# MainConnector.net
KiCad netlist of a schematic drawn in Altium Designer
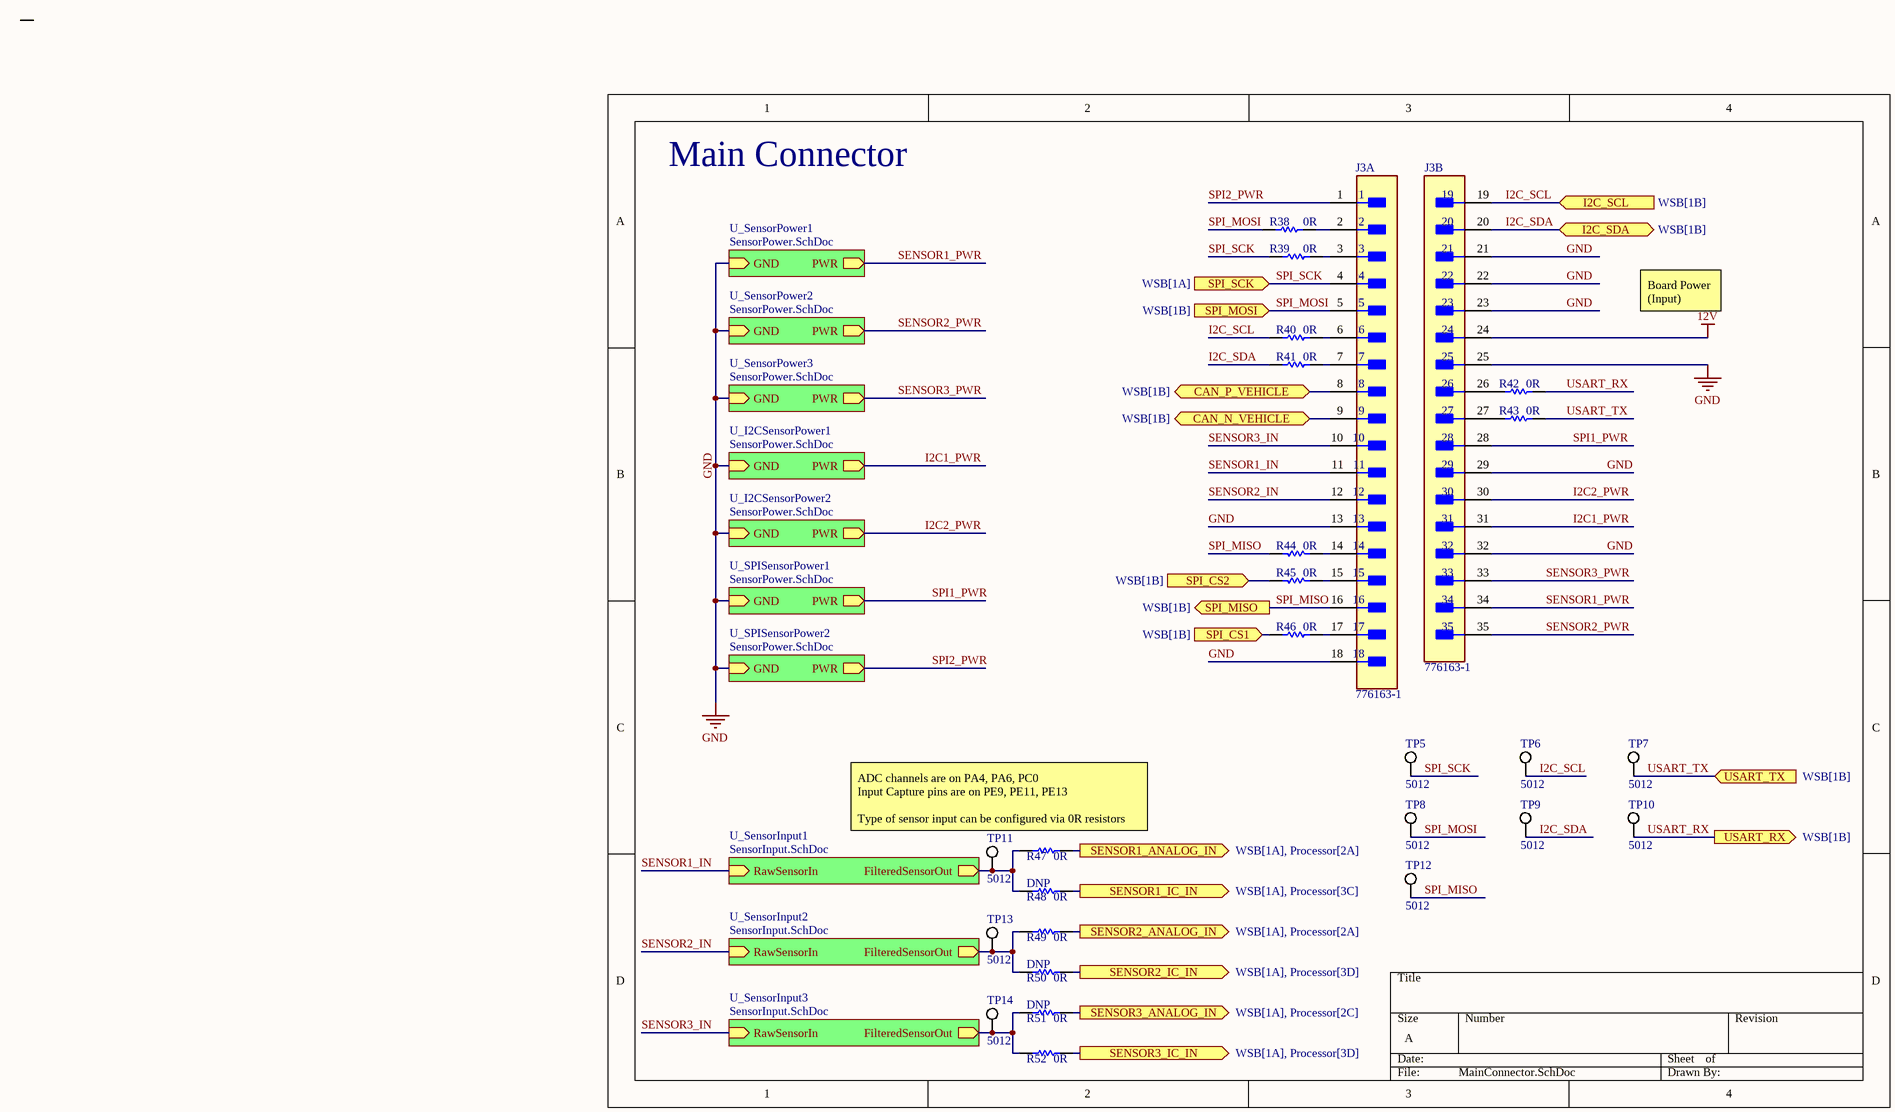
[diagram p0: MainConnector.SchDoc]

(export (version "E")
  (design (tool "Eeschema 10.0.6"))
  (components
    (comp (ref "J3")
      (value "776163-1")
      (footprint "FP-776163-1-MFG")
      (description "CONN HEADER R/A 35POS 4MM")
      (libsource (lib "") (part "519b18991870a11d3ebcd8ad3c0113e_1"))
    )
    (comp (ref "R38")
      (value "RC0805JR-100RL")
      (footprint "RESC2013X60X35LL10T20")
      (description "Chip Resistor, 0 Ohm, +/- 5%, 125 mW, -55 to 155 degC, 0805 (2012 Metric), RoHS, Tape and Reel")
      (fields (field (name "MANUFACTURER") "Yageo") (field (name "RESISTANCE") "0R"))
      (libsource (lib "Altium Content Vault") (part "RES-2"))
    )
    (comp (ref "R39")
      (value "RC0805JR-100RL")
      (footprint "RESC2013X60X35LL10T20")
      (description "Chip Resistor, 0 Ohm, +/- 5%, 125 mW, -55 to 155 degC, 0805 (2012 Metric), RoHS, Tape and Reel")
      (fields (field (name "MANUFACTURER") "Yageo") (field (name "RESISTANCE") "0R"))
      (libsource (lib "Altium Content Vault") (part "RES-2"))
    )
    (comp (ref "R40")
      (value "RC0805JR-100RL")
      (footprint "RESC2013X60X35LL10T20")
      (description "Chip Resistor, 0 Ohm, +/- 5%, 125 mW, -55 to 155 degC, 0805 (2012 Metric), RoHS, Tape and Reel")
      (fields (field (name "MANUFACTURER") "Yageo") (field (name "RESISTANCE") "0R"))
      (libsource (lib "Altium Content Vault") (part "RES-2"))
    )
    (comp (ref "R41")
      (value "RC0805JR-100RL")
      (footprint "RESC2013X60X35LL10T20")
      (description "Chip Resistor, 0 Ohm, +/- 5%, 125 mW, -55 to 155 degC, 0805 (2012 Metric), RoHS, Tape and Reel")
      (fields (field (name "MANUFACTURER") "Yageo") (field (name "RESISTANCE") "0R"))
      (libsource (lib "Altium Content Vault") (part "RES-2"))
    )
    (comp (ref "R42")
      (value "RC0805JR-100RL")
      (footprint "RESC2013X60X35LL10T20")
      (description "Chip Resistor, 0 Ohm, +/- 5%, 125 mW, -55 to 155 degC, 0805 (2012 Metric), RoHS, Tape and Reel")
      (fields (field (name "MANUFACTURER") "Yageo") (field (name "RESISTANCE") "0R"))
      (libsource (lib "Altium Content Vault") (part "RES-2"))
    )
    (comp (ref "R43")
      (value "RC0805JR-100RL")
      (footprint "RESC2013X60X35LL10T20")
      (description "Chip Resistor, 0 Ohm, +/- 5%, 125 mW, -55 to 155 degC, 0805 (2012 Metric), RoHS, Tape and Reel")
      (fields (field (name "MANUFACTURER") "Yageo") (field (name "RESISTANCE") "0R"))
      (libsource (lib "Altium Content Vault") (part "RES-2"))
    )
    (comp (ref "R44")
      (value "RC0805JR-100RL")
      (footprint "RESC2013X60X35LL10T20")
      (description "Chip Resistor, 0 Ohm, +/- 5%, 125 mW, -55 to 155 degC, 0805 (2012 Metric), RoHS, Tape and Reel")
      (fields (field (name "MANUFACTURER") "Yageo") (field (name "RESISTANCE") "0R"))
      (libsource (lib "Altium Content Vault") (part "RES-2"))
    )
    (comp (ref "R45")
      (value "RC0805JR-100RL")
      (footprint "RESC2013X60X35LL10T20")
      (description "Chip Resistor, 0 Ohm, +/- 5%, 125 mW, -55 to 155 degC, 0805 (2012 Metric), RoHS, Tape and Reel")
      (fields (field (name "MANUFACTURER") "Yageo") (field (name "RESISTANCE") "0R"))
      (libsource (lib "Altium Content Vault") (part "RES-2"))
    )
    (comp (ref "R46")
      (value "RC0805JR-100RL")
      (footprint "RESC2013X60X35LL10T20")
      (description "Chip Resistor, 0 Ohm, +/- 5%, 125 mW, -55 to 155 degC, 0805 (2012 Metric), RoHS, Tape and Reel")
      (fields (field (name "MANUFACTURER") "Yageo") (field (name "RESISTANCE") "0R"))
      (libsource (lib "Altium Content Vault") (part "RES-2"))
    )
    (comp (ref "R47")
      (value "RC0805JR-100RL")
      (footprint "RESC2013X60X35LL10T20")
      (description "Chip Resistor, 0 Ohm, +/- 5%, 125 mW, -55 to 155 degC, 0805 (2012 Metric), RoHS, Tape and Reel")
      (fields (field (name "MANUFACTURER") "Yageo") (field (name "RESISTANCE") "0R"))
      (libsource (lib "Altium Content Vault") (part "RES-2"))
    )
    (comp (ref "R48")
      (value "RC0805JR-100RL")
      (footprint "RESC2013X60X35LL10T20")
      (description "Chip Resistor, 0 Ohm, +/- 5%, 125 mW, -55 to 155 degC, 0805 (2012 Metric), RoHS, Tape and Reel")
      (fields
        (field (name "MANUFACTURER") "Yageo")
        (field (name "RESISTANCE") "0R")
        (field (name "DNP") "DNP")
      )
      (libsource (lib "Altium Content Vault") (part "RES-2"))
    )
    (comp (ref "R49")
      (value "RC0805JR-100RL")
      (footprint "RESC2013X60X35LL10T20")
      (description "Chip Resistor, 0 Ohm, +/- 5%, 125 mW, -55 to 155 degC, 0805 (2012 Metric), RoHS, Tape and Reel")
      (fields (field (name "MANUFACTURER") "Yageo") (field (name "RESISTANCE") "0R"))
      (libsource (lib "Altium Content Vault") (part "RES-2"))
    )
    (comp (ref "R50")
      (value "RC0805JR-100RL")
      (footprint "RESC2013X60X35LL10T20")
      (description "Chip Resistor, 0 Ohm, +/- 5%, 125 mW, -55 to 155 degC, 0805 (2012 Metric), RoHS, Tape and Reel")
      (fields
        (field (name "MANUFACTURER") "Yageo")
        (field (name "RESISTANCE") "0R")
        (field (name "DNP") "DNP")
      )
      (libsource (lib "Altium Content Vault") (part "RES-2"))
    )
    (comp (ref "R51")
      (value "RC0805JR-100RL")
      (footprint "RESC2013X60X35LL10T20")
      (description "Chip Resistor, 0 Ohm, +/- 5%, 125 mW, -55 to 155 degC, 0805 (2012 Metric), RoHS, Tape and Reel")
      (fields
        (field (name "MANUFACTURER") "Yageo")
        (field (name "RESISTANCE") "0R")
        (field (name "DNP") "DNP")
      )
      (libsource (lib "Altium Content Vault") (part "RES-2"))
    )
    (comp (ref "R52")
      (value "RC0805JR-100RL")
      (footprint "RESC2013X60X35LL10T20")
      (description "Chip Resistor, 0 Ohm, +/- 5%, 125 mW, -55 to 155 degC, 0805 (2012 Metric), RoHS, Tape and Reel")
      (fields (field (name "MANUFACTURER") "Yageo") (field (name "RESISTANCE") "0R"))
      (libsource (lib "Altium Content Vault") (part "RES-2"))
    )
    (comp (ref "TP5")
      (value "5012")
      (footprint "KSTN-5012_V")
      (description "Test Point, White, Through Hole, RoHS, Bulk")
      (fields (field (name "MANUFACTURER") "Keystone"))
      (libsource (lib "Altium Content Vault") (part "TESTPOINT_WHITE"))
    )
    (comp (ref "TP6")
      (value "5012")
      (footprint "KSTN-5012_V")
      (description "Test Point, White, Through Hole, RoHS, Bulk")
      (fields (field (name "MANUFACTURER") "Keystone"))
      (libsource (lib "Altium Content Vault") (part "TESTPOINT_WHITE"))
    )
    (comp (ref "TP7")
      (value "5012")
      (footprint "KSTN-5012_V")
      (description "Test Point, White, Through Hole, RoHS, Bulk")
      (fields (field (name "MANUFACTURER") "Keystone"))
      (libsource (lib "Altium Content Vault") (part "TESTPOINT_WHITE"))
    )
    (comp (ref "TP8")
      (value "5012")
      (footprint "KSTN-5012_V")
      (description "Test Point, White, Through Hole, RoHS, Bulk")
      (fields (field (name "MANUFACTURER") "Keystone"))
      (libsource (lib "Altium Content Vault") (part "TESTPOINT_WHITE"))
    )
    (comp (ref "TP9")
      (value "5012")
      (footprint "KSTN-5012_V")
      (description "Test Point, White, Through Hole, RoHS, Bulk")
      (fields (field (name "MANUFACTURER") "Keystone"))
      (libsource (lib "Altium Content Vault") (part "TESTPOINT_WHITE"))
    )
    (comp (ref "TP10")
      (value "5012")
      (footprint "KSTN-5012_V")
      (description "Test Point, White, Through Hole, RoHS, Bulk")
      (fields (field (name "MANUFACTURER") "Keystone"))
      (libsource (lib "Altium Content Vault") (part "TESTPOINT_WHITE"))
    )
    (comp (ref "TP11")
      (value "5012")
      (footprint "KSTN-5012_V")
      (description "Test Point, White, Through Hole, RoHS, Bulk")
      (fields (field (name "MANUFACTURER") "Keystone"))
      (libsource (lib "Altium Content Vault") (part "TESTPOINT_WHITE"))
    )
    (comp (ref "TP12")
      (value "5012")
      (footprint "KSTN-5012_V")
      (description "Test Point, White, Through Hole, RoHS, Bulk")
      (fields (field (name "MANUFACTURER") "Keystone"))
      (libsource (lib "Altium Content Vault") (part "TESTPOINT_WHITE"))
    )
    (comp (ref "TP13")
      (value "5012")
      (footprint "KSTN-5012_V")
      (description "Test Point, White, Through Hole, RoHS, Bulk")
      (fields (field (name "MANUFACTURER") "Keystone"))
      (libsource (lib "Altium Content Vault") (part "TESTPOINT_WHITE"))
    )
    (comp (ref "TP14")
      (value "5012")
      (footprint "KSTN-5012_V")
      (description "Test Point, White, Through Hole, RoHS, Bulk")
      (fields (field (name "MANUFACTURER") "Keystone"))
      (libsource (lib "Altium Content Vault") (part "TESTPOINT_WHITE"))
    )
  )
  (nets
    (net (code "1") (name "/CAN_N_VEHICLE") (class "Default")
      (node (ref "J3") (pin "9") (pinfunction "9_9") (pintype "passive"))
    )
    (net (code "2") (name "/CAN_P_VEHICLE") (class "Default")
      (node (ref "J3") (pin "8") (pinfunction "8_8") (pintype "passive"))
    )
    (net (code "3") (name "/FilteredSensorOut") (class "Default")
      (node (ref "R47") (pin "2") (pinfunction "2_2") (pintype "passive"))
      (node (ref "R48") (pin "2") (pinfunction "2_2") (pintype "passive"))
      (node (ref "TP11") (pin "1") (pinfunction "1_1") (pintype "passive"))
    )
    (net (code "4") (name "/FilteredSensorOut_1") (class "Default")
      (node (ref "R51") (pin "2") (pinfunction "2_2") (pintype "passive"))
      (node (ref "R52") (pin "2") (pinfunction "2_2") (pintype "passive"))
      (node (ref "TP14") (pin "1") (pinfunction "1_1") (pintype "passive"))
    )
    (net (code "5") (name "/FilteredSensorOut_2") (class "Default")
      (node (ref "R49") (pin "2") (pinfunction "2_2") (pintype "passive"))
      (node (ref "R50") (pin "2") (pinfunction "2_2") (pintype "passive"))
      (node (ref "TP13") (pin "1") (pinfunction "1_1") (pintype "passive"))
    )
    (net (code "6") (name "/I2C1_PWR") (class "Default")
      (node (ref "J3") (pin "31") (pinfunction "31_31") (pintype "passive"))
    )
    (net (code "7") (name "/I2C2_PWR") (class "Default")
      (node (ref "J3") (pin "30") (pinfunction "30_30") (pintype "passive"))
    )
    (net (code "8") (name "/I2C_SCL") (class "Default")
      (node (ref "J3") (pin "19") (pinfunction "19_19") (pintype "passive"))
      (node (ref "R40") (pin "2") (pinfunction "2_2") (pintype "passive"))
      (node (ref "TP6") (pin "1") (pinfunction "1_1") (pintype "passive"))
    )
    (net (code "9") (name "/I2C_SDA") (class "Default")
      (node (ref "J3") (pin "20") (pinfunction "20_20") (pintype "passive"))
      (node (ref "R41") (pin "2") (pinfunction "2_2") (pintype "passive"))
      (node (ref "TP9") (pin "1") (pinfunction "1_1") (pintype "passive"))
    )
    (net (code "10") (name "/SENSOR1_ANALOG_IN") (class "Default")
      (node (ref "R47") (pin "1") (pinfunction "1_1") (pintype "passive"))
    )
    (net (code "11") (name "/SENSOR1_IC_IN") (class "Default")
      (node (ref "R48") (pin "1") (pinfunction "1_1") (pintype "passive"))
    )
    (net (code "12") (name "/SENSOR1_IN") (class "Default")
      (node (ref "J3") (pin "11") (pinfunction "11_11") (pintype "passive"))
    )
    (net (code "13") (name "/SENSOR1_PWR") (class "Default")
      (node (ref "J3") (pin "34") (pinfunction "34_34") (pintype "passive"))
    )
    (net (code "14") (name "/SENSOR2_ANALOG_IN") (class "Default")
      (node (ref "R49") (pin "1") (pinfunction "1_1") (pintype "passive"))
    )
    (net (code "15") (name "/SENSOR2_IC_IN") (class "Default")
      (node (ref "R50") (pin "1") (pinfunction "1_1") (pintype "passive"))
    )
    (net (code "16") (name "/SENSOR2_IN") (class "Default")
      (node (ref "J3") (pin "12") (pinfunction "12_12") (pintype "passive"))
    )
    (net (code "17") (name "/SENSOR2_PWR") (class "Default")
      (node (ref "J3") (pin "35") (pinfunction "35_35") (pintype "passive"))
    )
    (net (code "18") (name "/SENSOR3_ANALOG_IN") (class "Default")
      (node (ref "R51") (pin "1") (pinfunction "1_1") (pintype "passive"))
    )
    (net (code "19") (name "/SENSOR3_IC_IN") (class "Default")
      (node (ref "R52") (pin "1") (pinfunction "1_1") (pintype "passive"))
    )
    (net (code "20") (name "/SENSOR3_IN") (class "Default")
      (node (ref "J3") (pin "10") (pinfunction "10_10") (pintype "passive"))
    )
    (net (code "21") (name "/SENSOR3_PWR") (class "Default")
      (node (ref "J3") (pin "33") (pinfunction "33_33") (pintype "passive"))
    )
    (net (code "22") (name "/SPI1_PWR") (class "Default")
      (node (ref "J3") (pin "28") (pinfunction "28_28") (pintype "passive"))
    )
    (net (code "23") (name "/SPI2_PWR") (class "Default")
      (node (ref "J3") (pin "1") (pinfunction "1_1") (pintype "passive"))
    )
    (net (code "24") (name "/SPI_CS1") (class "Default")
      (node (ref "R46") (pin "2") (pinfunction "2_2") (pintype "passive"))
    )
    (net (code "25") (name "/SPI_CS2") (class "Default")
      (node (ref "R45") (pin "1") (pinfunction "1_1") (pintype "passive"))
    )
    (net (code "26") (name "/SPI_MISO") (class "Default")
      (node (ref "J3") (pin "16") (pinfunction "16_16") (pintype "passive"))
      (node (ref "R44") (pin "1") (pinfunction "1_1") (pintype "passive"))
      (node (ref "TP12") (pin "1") (pinfunction "1_1") (pintype "passive"))
    )
    (net (code "27") (name "/SPI_MOSI") (class "Default")
      (node (ref "J3") (pin "5") (pinfunction "5_5") (pintype "passive"))
      (node (ref "R38") (pin "2") (pinfunction "2_2") (pintype "passive"))
      (node (ref "TP8") (pin "1") (pinfunction "1_1") (pintype "passive"))
    )
    (net (code "28") (name "/SPI_SCK") (class "Default")
      (node (ref "J3") (pin "4") (pinfunction "4_4") (pintype "passive"))
      (node (ref "R39") (pin "1") (pinfunction "1_1") (pintype "passive"))
      (node (ref "TP5") (pin "1") (pinfunction "1_1") (pintype "passive"))
    )
    (net (code "29") (name "/USART_RX") (class "Default")
      (node (ref "R42") (pin "1") (pinfunction "1_1") (pintype "passive"))
      (node (ref "TP10") (pin "1") (pinfunction "1_1") (pintype "passive"))
    )
    (net (code "30") (name "/USART_TX") (class "Default")
      (node (ref "R43") (pin "1") (pinfunction "1_1") (pintype "passive"))
      (node (ref "TP7") (pin "1") (pinfunction "1_1") (pintype "passive"))
    )
    (net (code "31") (name "12V") (class "Default")
      (node (ref "J3") (pin "24") (pinfunction "24_24") (pintype "passive"))
    )
    (net (code "32") (name "GND") (class "Default")
      (node (ref "J3") (pin "13") (pinfunction "13_13") (pintype "passive"))
      (node (ref "J3") (pin "18") (pinfunction "18_18") (pintype "passive"))
      (node (ref "J3") (pin "21") (pinfunction "21_21") (pintype "passive"))
      (node (ref "J3") (pin "22") (pinfunction "22_22") (pintype "passive"))
      (node (ref "J3") (pin "23") (pinfunction "23_23") (pintype "passive"))
      (node (ref "J3") (pin "25") (pinfunction "25_25") (pintype "passive"))
      (node (ref "J3") (pin "29") (pinfunction "29_29") (pintype "passive"))
      (node (ref "J3") (pin "32") (pinfunction "32_32") (pintype "passive"))
    )
    (net (code "33") (name "Net-(J3-Pad2)") (class "Default")
      (node (ref "J3") (pin "2") (pinfunction "2_2") (pintype "passive"))
      (node (ref "R38") (pin "1") (pinfunction "1_1") (pintype "passive"))
    )
    (net (code "34") (name "Net-(J3-Pad3)") (class "Default")
      (node (ref "J3") (pin "3") (pinfunction "3_3") (pintype "passive"))
      (node (ref "R39") (pin "2") (pinfunction "2_2") (pintype "passive"))
    )
    (net (code "35") (name "Net-(J3-Pad6)") (class "Default")
      (node (ref "J3") (pin "6") (pinfunction "6_6") (pintype "passive"))
      (node (ref "R40") (pin "1") (pinfunction "1_1") (pintype "passive"))
    )
    (net (code "36") (name "Net-(J3-Pad7)") (class "Default")
      (node (ref "J3") (pin "7") (pinfunction "7_7") (pintype "passive"))
      (node (ref "R41") (pin "1") (pinfunction "1_1") (pintype "passive"))
    )
    (net (code "37") (name "Net-(J3-Pad14)") (class "Default")
      (node (ref "J3") (pin "14") (pinfunction "14_14") (pintype "passive"))
      (node (ref "R44") (pin "2") (pinfunction "2_2") (pintype "passive"))
    )
    (net (code "38") (name "Net-(J3-Pad15)") (class "Default")
      (node (ref "J3") (pin "15") (pinfunction "15_15") (pintype "passive"))
      (node (ref "R45") (pin "2") (pinfunction "2_2") (pintype "passive"))
    )
    (net (code "39") (name "Net-(J3-Pad17)") (class "Default")
      (node (ref "J3") (pin "17") (pinfunction "17_17") (pintype "passive"))
      (node (ref "R46") (pin "1") (pinfunction "1_1") (pintype "passive"))
    )
    (net (code "40") (name "Net-(J3-Pad26)") (class "Default")
      (node (ref "J3") (pin "26") (pinfunction "26_26") (pintype "passive"))
      (node (ref "R42") (pin "2") (pinfunction "2_2") (pintype "passive"))
    )
    (net (code "41") (name "Net-(J3-Pad27)") (class "Default")
      (node (ref "J3") (pin "27") (pinfunction "27_27") (pintype "passive"))
      (node (ref "R43") (pin "2") (pinfunction "2_2") (pintype "passive"))
    )
  )
)
